# Adafruit_16x8_Monochrome_LED_Backpack.net
KiCad netlist of a schematic drawn in EAGLE
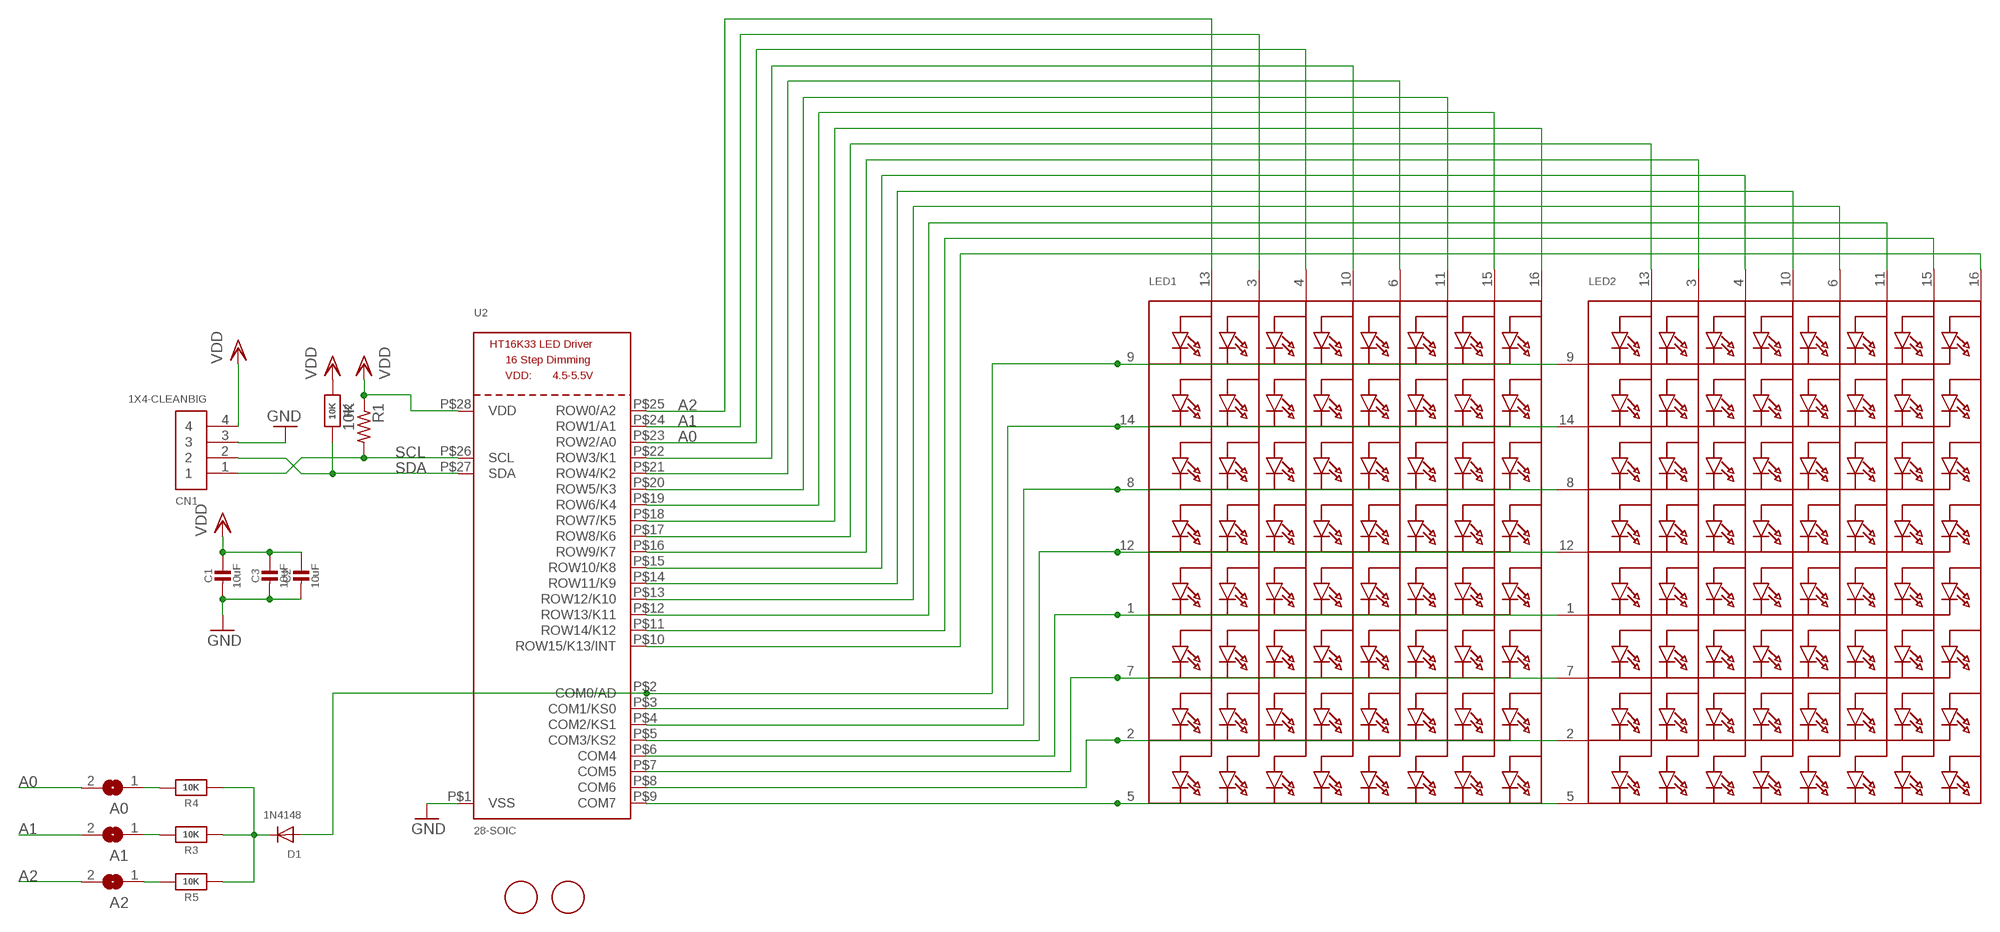
[diagram p0: schematic, sheet 1]

(export (version "E")
  (design (tool "Eeschema 10.0.6"))
  (components
    (comp (ref "A0")
      (value "SOLDERJUMPERREFLOW_NOPASTE")
      (footprint "eagle-import:SOLDERJUMPER_REFLOW_NOPASTE")
      (libsource (lib "eagle-import") (part "SOLDERJUMPERREFLOW_NOPASTE"))
    )
    (comp (ref "A1")
      (value "SOLDERJUMPERREFLOW_NOPASTE")
      (footprint "eagle-import:SOLDERJUMPER_REFLOW_NOPASTE")
      (libsource (lib "eagle-import") (part "SOLDERJUMPERREFLOW_NOPASTE"))
    )
    (comp (ref "A2")
      (value "SOLDERJUMPERREFLOW_NOPASTE")
      (footprint "eagle-import:SOLDERJUMPER_REFLOW_NOPASTE")
      (libsource (lib "eagle-import") (part "SOLDERJUMPERREFLOW_NOPASTE"))
    )
    (comp (ref "C1")
      (value "10uF")
      (footprint "eagle-import:0805-NO")
      (libsource (lib "eagle-import") (part "CAP_CERAMIC0805-NOOUTLINE"))
    )
    (comp (ref "C2")
      (value "10uF")
      (footprint "eagle-import:0805-NO")
      (libsource (lib "eagle-import") (part "CAP_CERAMIC0805-NOOUTLINE"))
    )
    (comp (ref "C3")
      (value "10uF")
      (footprint "eagle-import:0805-NO")
      (libsource (lib "eagle-import") (part "CAP_CERAMIC0805-NOOUTLINE"))
    )
    (comp (ref "CN1")
      (value "1X4-CLEANBIG")
      (footprint "eagle-import:1X04-CLEANBIG")
      (libsource (lib "eagle-import") (part "1X4-CLEANBIG"))
    )
    (comp (ref "D1")
      (value "1N4148")
      (footprint "eagle-import:SOD-323F")
      (libsource (lib "eagle-import") (part "DIODESOD-323F"))
    )
    (comp (ref "LED1")
      (value "DISP_SEGMENT_8X8_ROWCATHODEM12A881UR")
      (footprint "eagle-import:SEGMENT_BL-M12A881UR")
      (libsource (lib "eagle-import") (part "DISP_SEGMENT_8X8_ROWCATHODEM12A881UR"))
    )
    (comp (ref "LED2")
      (value "DISP_SEGMENT_8X8_ROWCATHODEM12A881UR")
      (footprint "eagle-import:SEGMENT_BL-M12A881UR")
      (libsource (lib "eagle-import") (part "DISP_SEGMENT_8X8_ROWCATHODEM12A881UR"))
    )
    (comp (ref "R1")
      (value "10K")
      (footprint "eagle-import:R0805")
      (libsource (lib "eagle-import") (part "R-US_R0805"))
    )
    (comp (ref "R2")
      (value "10K")
      (footprint "eagle-import:0805-NO")
      (libsource (lib "eagle-import") (part "RESISTOR0805_NOOUTLINE"))
    )
    (comp (ref "R3")
      (value "10K")
      (footprint "eagle-import:0805-NO")
      (libsource (lib "eagle-import") (part "RESISTOR0805_NOOUTLINE"))
    )
    (comp (ref "R4")
      (value "10K")
      (footprint "eagle-import:0805-NO")
      (libsource (lib "eagle-import") (part "RESISTOR0805_NOOUTLINE"))
    )
    (comp (ref "R5")
      (value "10K")
      (footprint "eagle-import:0805-NO")
      (libsource (lib "eagle-import") (part "RESISTOR0805_NOOUTLINE"))
    )
    (comp (ref "U$1")
      (value "FIDUCIAL")
      (footprint "eagle-import:FIDUCIAL_1MM")
      (libsource (lib "eagle-import") (part "FIDUCIAL"))
    )
    (comp (ref "U$2")
      (value "FIDUCIAL")
      (footprint "eagle-import:FIDUCIAL_1MM")
      (libsource (lib "eagle-import") (part "FIDUCIAL"))
    )
    (comp (ref "U2")
      (value "28-SOIC")
      (footprint "eagle-import:SOP28_300MIL")
      (libsource (lib "eagle-import") (part "HT16K33_SOP28"))
    )
  )
  (nets
    (net (code "1") (name "/A0") (class "Default")
      (node (ref "A0") (pin "2") (pinfunction "2_2") (pintype "passive"))
      (node (ref "LED1") (pin "4") (pinfunction "A3_4") (pintype "bidirectional"))
      (node (ref "U2") (pin "P$23") (pinfunction "ROW2/A0_P$23") (pintype "bidirectional"))
    )
    (net (code "2") (name "/A1") (class "Default")
      (node (ref "A1") (pin "2") (pinfunction "2_2") (pintype "passive"))
      (node (ref "LED1") (pin "3") (pinfunction "A2_3") (pintype "bidirectional"))
      (node (ref "U2") (pin "P$24") (pinfunction "ROW1/A1_P$24") (pintype "bidirectional"))
    )
    (net (code "3") (name "/A2") (class "Default")
      (node (ref "A2") (pin "2") (pinfunction "2_2") (pintype "passive"))
      (node (ref "LED1") (pin "13") (pinfunction "A1_13") (pintype "bidirectional"))
      (node (ref "U2") (pin "P$25") (pinfunction "ROW0/A2_P$25") (pintype "bidirectional"))
    )
    (net (code "4") (name "/SCL") (class "Default")
      (node (ref "CN1") (pin "1") (pinfunction "1_1") (pintype "bidirectional"))
      (node (ref "R1") (pin "2") (pinfunction "2_2") (pintype "passive"))
      (node (ref "U2") (pin "P$26") (pinfunction "SCL_P$26") (pintype "bidirectional"))
    )
    (net (code "5") (name "/SDA") (class "Default")
      (node (ref "CN1") (pin "2") (pinfunction "2_2") (pintype "bidirectional"))
      (node (ref "R2") (pin "2") (pinfunction "2_2") (pintype "passive"))
      (node (ref "U2") (pin "P$27") (pinfunction "SDA_P$27") (pintype "bidirectional"))
    )
    (net (code "6") (name "GND") (class "Default")
      (node (ref "C1") (pin "2") (pinfunction "2_2") (pintype "passive"))
      (node (ref "C2") (pin "2") (pinfunction "2_2") (pintype "passive"))
      (node (ref "C3") (pin "2") (pinfunction "2_2") (pintype "passive"))
      (node (ref "CN1") (pin "3") (pinfunction "3_3") (pintype "bidirectional"))
      (node (ref "U2") (pin "P$1") (pinfunction "VSS_P$1") (pintype "bidirectional"))
    )
    (net (code "7") (name "Net-(A0-Pad1)") (class "Default")
      (node (ref "A0") (pin "1") (pinfunction "1_1") (pintype "passive"))
      (node (ref "R4") (pin "2") (pinfunction "2_2") (pintype "passive"))
    )
    (net (code "8") (name "Net-(A1-Pad1)") (class "Default")
      (node (ref "A1") (pin "1") (pinfunction "1_1") (pintype "passive"))
      (node (ref "R3") (pin "2") (pinfunction "2_2") (pintype "passive"))
    )
    (net (code "9") (name "Net-(A2-Pad1)") (class "Default")
      (node (ref "A2") (pin "1") (pinfunction "1_1") (pintype "passive"))
      (node (ref "R5") (pin "2") (pinfunction "2_2") (pintype "passive"))
    )
    (net (code "10") (name "Net-(D1-PadC)") (class "Default")
      (node (ref "D1") (pin "C") (pinfunction "C_C") (pintype "passive"))
      (node (ref "R3") (pin "1") (pinfunction "1_1") (pintype "passive"))
      (node (ref "R4") (pin "1") (pinfunction "1_1") (pintype "passive"))
      (node (ref "R5") (pin "1") (pinfunction "1_1") (pintype "passive"))
    )
    (net (code "11") (name "Net-(LED1-A4)") (class "Default")
      (node (ref "LED1") (pin "10") (pinfunction "A4_10") (pintype "bidirectional"))
      (node (ref "U2") (pin "P$22") (pinfunction "ROW3/K1_P$22") (pintype "bidirectional"))
    )
    (net (code "12") (name "Net-(LED1-A5)") (class "Default")
      (node (ref "LED1") (pin "6") (pinfunction "A5_6") (pintype "bidirectional"))
      (node (ref "U2") (pin "P$21") (pinfunction "ROW4/K2_P$21") (pintype "bidirectional"))
    )
    (net (code "13") (name "Net-(LED1-A6)") (class "Default")
      (node (ref "LED1") (pin "11") (pinfunction "A6_11") (pintype "bidirectional"))
      (node (ref "U2") (pin "P$20") (pinfunction "ROW5/K3_P$20") (pintype "bidirectional"))
    )
    (net (code "14") (name "Net-(LED1-A7)") (class "Default")
      (node (ref "LED1") (pin "15") (pinfunction "A7_15") (pintype "bidirectional"))
      (node (ref "U2") (pin "P$19") (pinfunction "ROW6/K4_P$19") (pintype "bidirectional"))
    )
    (net (code "15") (name "Net-(LED1-A8)") (class "Default")
      (node (ref "LED1") (pin "16") (pinfunction "A8_16") (pintype "bidirectional"))
      (node (ref "U2") (pin "P$18") (pinfunction "ROW7/K5_P$18") (pintype "bidirectional"))
    )
    (net (code "16") (name "Net-(LED1-K1)") (class "Default")
      (node (ref "D1") (pin "A") (pinfunction "A_A") (pintype "passive"))
      (node (ref "LED1") (pin "9") (pinfunction "K1_9") (pintype "bidirectional"))
      (node (ref "LED2") (pin "9") (pinfunction "K1_9") (pintype "bidirectional"))
      (node (ref "U2") (pin "P$2") (pinfunction "COM0/AD_P$2") (pintype "bidirectional"))
    )
    (net (code "17") (name "Net-(LED1-K2)") (class "Default")
      (node (ref "LED1") (pin "14") (pinfunction "K2_14") (pintype "bidirectional"))
      (node (ref "LED2") (pin "14") (pinfunction "K2_14") (pintype "bidirectional"))
      (node (ref "U2") (pin "P$3") (pinfunction "COM1/KS0_P$3") (pintype "bidirectional"))
    )
    (net (code "18") (name "Net-(LED1-K3)") (class "Default")
      (node (ref "LED1") (pin "8") (pinfunction "K3_8") (pintype "bidirectional"))
      (node (ref "LED2") (pin "8") (pinfunction "K3_8") (pintype "bidirectional"))
      (node (ref "U2") (pin "P$4") (pinfunction "COM2/KS1_P$4") (pintype "bidirectional"))
    )
    (net (code "19") (name "Net-(LED1-K4)") (class "Default")
      (node (ref "LED1") (pin "12") (pinfunction "K4_12") (pintype "bidirectional"))
      (node (ref "LED2") (pin "12") (pinfunction "K4_12") (pintype "bidirectional"))
      (node (ref "U2") (pin "P$5") (pinfunction "COM3/KS2_P$5") (pintype "bidirectional"))
    )
    (net (code "20") (name "Net-(LED1-K5)") (class "Default")
      (node (ref "LED1") (pin "1") (pinfunction "K5_1") (pintype "bidirectional"))
      (node (ref "LED2") (pin "1") (pinfunction "K5_1") (pintype "bidirectional"))
      (node (ref "U2") (pin "P$6") (pinfunction "COM4_P$6") (pintype "bidirectional"))
    )
    (net (code "21") (name "Net-(LED1-K6)") (class "Default")
      (node (ref "LED1") (pin "7") (pinfunction "K6_7") (pintype "bidirectional"))
      (node (ref "LED2") (pin "7") (pinfunction "K6_7") (pintype "bidirectional"))
      (node (ref "U2") (pin "P$7") (pinfunction "COM5_P$7") (pintype "bidirectional"))
    )
    (net (code "22") (name "Net-(LED1-K7)") (class "Default")
      (node (ref "LED1") (pin "2") (pinfunction "K7_2") (pintype "bidirectional"))
      (node (ref "LED2") (pin "2") (pinfunction "K7_2") (pintype "bidirectional"))
      (node (ref "U2") (pin "P$8") (pinfunction "COM6_P$8") (pintype "bidirectional"))
    )
    (net (code "23") (name "Net-(LED1-K8)") (class "Default")
      (node (ref "LED1") (pin "5") (pinfunction "K8_5") (pintype "bidirectional"))
      (node (ref "LED2") (pin "5") (pinfunction "K8_5") (pintype "bidirectional"))
      (node (ref "U2") (pin "P$9") (pinfunction "COM7_P$9") (pintype "bidirectional"))
    )
    (net (code "24") (name "Net-(LED2-A1)") (class "Default")
      (node (ref "LED2") (pin "13") (pinfunction "A1_13") (pintype "bidirectional"))
      (node (ref "U2") (pin "P$17") (pinfunction "ROW8/K6_P$17") (pintype "bidirectional"))
    )
    (net (code "25") (name "Net-(LED2-A2)") (class "Default")
      (node (ref "LED2") (pin "3") (pinfunction "A2_3") (pintype "bidirectional"))
      (node (ref "U2") (pin "P$16") (pinfunction "ROW9/K7_P$16") (pintype "bidirectional"))
    )
    (net (code "26") (name "Net-(LED2-A3)") (class "Default")
      (node (ref "LED2") (pin "4") (pinfunction "A3_4") (pintype "bidirectional"))
      (node (ref "U2") (pin "P$15") (pinfunction "ROW10/K8_P$15") (pintype "bidirectional"))
    )
    (net (code "27") (name "Net-(LED2-A4)") (class "Default")
      (node (ref "LED2") (pin "10") (pinfunction "A4_10") (pintype "bidirectional"))
      (node (ref "U2") (pin "P$14") (pinfunction "ROW11/K9_P$14") (pintype "bidirectional"))
    )
    (net (code "28") (name "Net-(LED2-A5)") (class "Default")
      (node (ref "LED2") (pin "6") (pinfunction "A5_6") (pintype "bidirectional"))
      (node (ref "U2") (pin "P$13") (pinfunction "ROW12/K10_P$13") (pintype "bidirectional"))
    )
    (net (code "29") (name "Net-(LED2-A6)") (class "Default")
      (node (ref "LED2") (pin "11") (pinfunction "A6_11") (pintype "bidirectional"))
      (node (ref "U2") (pin "P$12") (pinfunction "ROW13/K11_P$12") (pintype "bidirectional"))
    )
    (net (code "30") (name "Net-(LED2-A7)") (class "Default")
      (node (ref "LED2") (pin "15") (pinfunction "A7_15") (pintype "bidirectional"))
      (node (ref "U2") (pin "P$11") (pinfunction "ROW14/K12_P$11") (pintype "bidirectional"))
    )
    (net (code "31") (name "Net-(LED2-A8)") (class "Default")
      (node (ref "LED2") (pin "16") (pinfunction "A8_16") (pintype "bidirectional"))
      (node (ref "U2") (pin "P$10") (pinfunction "ROW15/K13/INT_P$10") (pintype "bidirectional"))
    )
    (net (code "32") (name "VDD") (class "Default")
      (node (ref "C1") (pin "1") (pinfunction "1_1") (pintype "passive"))
      (node (ref "C2") (pin "1") (pinfunction "1_1") (pintype "passive"))
      (node (ref "C3") (pin "1") (pinfunction "1_1") (pintype "passive"))
      (node (ref "CN1") (pin "4") (pinfunction "4_4") (pintype "bidirectional"))
      (node (ref "R1") (pin "1") (pinfunction "1_1") (pintype "passive"))
      (node (ref "R2") (pin "1") (pinfunction "1_1") (pintype "passive"))
      (node (ref "U2") (pin "P$28") (pinfunction "VDD_P$28") (pintype "bidirectional"))
    )
  )
)
